# Controller_Board_Interface.net
KiCad netlist of a schematic drawn in Altium Designer
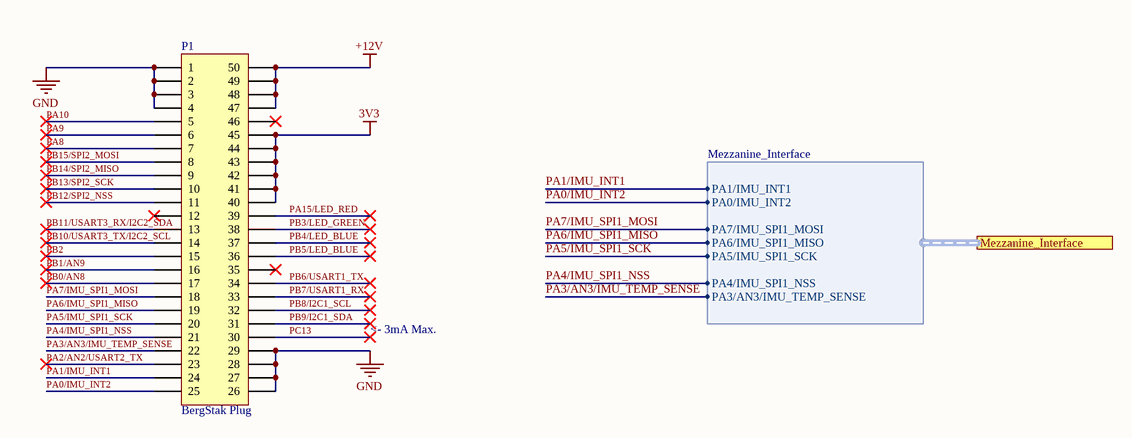
[diagram p0: Controller_Board_Interface.SchDoc]

(export (version "E")
  (design (tool "Eeschema 10.0.6"))
  (components
    (comp (ref "P1")
      (value "CONN 50POS Bergstak Plug 0.02\"")
      (footprint "CONN, Bergstak 50 Pos Plug")
      (description "50 Position Connector Plug, Outer Shroud Contacts Surface Mount Gold")
      (fields (field (name "SERIES") "BergStak Plug"))
      (libsource (lib "Schematic Diagrams") (part "CONN 50POS Bergstak Plug 0.02{dblquote}"))
    )
  )
  (nets
    (net (code "2") (name "+12V") (class "Default")
      (node (ref "P1") (pin "47") (pinfunction "47_47") (pintype "passive"))
      (node (ref "P1") (pin "48") (pinfunction "48_48") (pintype "passive"))
      (node (ref "P1") (pin "49") (pinfunction "49_49") (pintype "passive"))
      (node (ref "P1") (pin "50") (pinfunction "50_50") (pintype "passive"))
    )
    (net (code "3") (name "/PA0{slash}IMU_INT2") (class "Default")
      (node (ref "P1") (pin "25") (pinfunction "25_25") (pintype "passive"))
    )
    (net (code "4") (name "/PA1{slash}IMU_INT1") (class "Default")
      (node (ref "P1") (pin "24") (pinfunction "24_24") (pintype "passive"))
    )
    (net (code "5") (name "/PA2{slash}AN2{slash}USART2_TX") (class "Default")
      (node (ref "P1") (pin "23") (pinfunction "23_23") (pintype "passive+no_connect"))
    )
    (net (code "6") (name "/PA3{slash}AN3{slash}IMU_TEMP_SENSE") (class "Default")
      (node (ref "P1") (pin "22") (pinfunction "22_22") (pintype "passive"))
    )
    (net (code "7") (name "/PA4{slash}IMU_SPI1_NSS") (class "Default")
      (node (ref "P1") (pin "21") (pinfunction "21_21") (pintype "passive"))
    )
    (net (code "8") (name "/PA5{slash}IMU_SPI1_SCK") (class "Default")
      (node (ref "P1") (pin "20") (pinfunction "20_20") (pintype "passive"))
    )
    (net (code "9") (name "/PA6{slash}IMU_SPI1_MISO") (class "Default")
      (node (ref "P1") (pin "19") (pinfunction "19_19") (pintype "passive"))
    )
    (net (code "10") (name "/PA7{slash}IMU_SPI1_MOSI") (class "Default")
      (node (ref "P1") (pin "18") (pinfunction "18_18") (pintype "passive"))
    )
    (net (code "11") (name "/PA8") (class "Default")
      (node (ref "P1") (pin "7") (pinfunction "7_7") (pintype "passive+no_connect"))
    )
    (net (code "12") (name "/PA9") (class "Default")
      (node (ref "P1") (pin "6") (pinfunction "6_6") (pintype "passive+no_connect"))
    )
    (net (code "13") (name "/PA10") (class "Default")
      (node (ref "P1") (pin "5") (pinfunction "5_5") (pintype "passive+no_connect"))
    )
    (net (code "14") (name "/PA15{slash}LED_RED") (class "Default")
      (node (ref "P1") (pin "39") (pinfunction "39_39") (pintype "passive+no_connect"))
    )
    (net (code "15") (name "/PB0{slash}AN8") (class "Default")
      (node (ref "P1") (pin "17") (pinfunction "17_17") (pintype "passive+no_connect"))
    )
    (net (code "16") (name "/PB1{slash}AN9") (class "Default")
      (node (ref "P1") (pin "16") (pinfunction "16_16") (pintype "passive+no_connect"))
    )
    (net (code "17") (name "/PB2") (class "Default")
      (node (ref "P1") (pin "15") (pinfunction "15_15") (pintype "passive+no_connect"))
    )
    (net (code "18") (name "/PB3{slash}LED_GREEN") (class "Default")
      (node (ref "P1") (pin "38") (pinfunction "38_38") (pintype "passive+no_connect"))
    )
    (net (code "19") (name "/PB4{slash}LED_BLUE") (class "Default")
      (node (ref "P1") (pin "37") (pinfunction "37_37") (pintype "passive+no_connect"))
    )
    (net (code "20") (name "/PB5{slash}LED_BLUE") (class "Default")
      (node (ref "P1") (pin "36") (pinfunction "36_36") (pintype "passive+no_connect"))
    )
    (net (code "21") (name "/PB6{slash}USART1_TX") (class "Default")
      (node (ref "P1") (pin "34") (pinfunction "34_34") (pintype "passive+no_connect"))
    )
    (net (code "22") (name "/PB7{slash}USART1_RX") (class "Default")
      (node (ref "P1") (pin "33") (pinfunction "33_33") (pintype "passive+no_connect"))
    )
    (net (code "23") (name "/PB8{slash}I2C1_SCL") (class "Default")
      (node (ref "P1") (pin "32") (pinfunction "32_32") (pintype "passive+no_connect"))
    )
    (net (code "24") (name "/PB9{slash}I2C1_SDA") (class "Default")
      (node (ref "P1") (pin "31") (pinfunction "31_31") (pintype "passive+no_connect"))
    )
    (net (code "25") (name "/PB10{slash}USART3_TX{slash}I2C2_SCL") (class "Default")
      (node (ref "P1") (pin "14") (pinfunction "14_14") (pintype "passive+no_connect"))
    )
    (net (code "26") (name "/PB11{slash}USART3_RX{slash}I2C2_SDA") (class "Default")
      (node (ref "P1") (pin "13") (pinfunction "13_13") (pintype "passive+no_connect"))
    )
    (net (code "27") (name "/PB12{slash}SPI2_NSS") (class "Default")
      (node (ref "P1") (pin "11") (pinfunction "11_11") (pintype "passive+no_connect"))
    )
    (net (code "28") (name "/PB13{slash}SPI2_SCK") (class "Default")
      (node (ref "P1") (pin "10") (pinfunction "10_10") (pintype "passive+no_connect"))
    )
    (net (code "29") (name "/PB14{slash}SPI2_MISO") (class "Default")
      (node (ref "P1") (pin "9") (pinfunction "9_9") (pintype "passive+no_connect"))
    )
    (net (code "30") (name "/PB15{slash}SPI2_MOSI") (class "Default")
      (node (ref "P1") (pin "8") (pinfunction "8_8") (pintype "passive+no_connect"))
    )
    (net (code "31") (name "/PC13") (class "Default")
      (node (ref "P1") (pin "30") (pinfunction "30_30") (pintype "passive+no_connect"))
    )
    (net (code "33") (name "3V3") (class "Default")
      (node (ref "P1") (pin "40") (pinfunction "40_40") (pintype "passive"))
      (node (ref "P1") (pin "41") (pinfunction "41_41") (pintype "passive"))
      (node (ref "P1") (pin "42") (pinfunction "42_42") (pintype "passive"))
      (node (ref "P1") (pin "43") (pinfunction "43_43") (pintype "passive"))
      (node (ref "P1") (pin "44") (pinfunction "44_44") (pintype "passive"))
      (node (ref "P1") (pin "45") (pinfunction "45_45") (pintype "passive"))
    )
    (net (code "34") (name "GND") (class "Default")
      (node (ref "P1") (pin "1") (pinfunction "1_1") (pintype "passive"))
      (node (ref "P1") (pin "2") (pinfunction "2_2") (pintype "passive"))
      (node (ref "P1") (pin "26") (pinfunction "26_26") (pintype "passive"))
      (node (ref "P1") (pin "27") (pinfunction "27_27") (pintype "passive"))
      (node (ref "P1") (pin "28") (pinfunction "28_28") (pintype "passive"))
      (node (ref "P1") (pin "29") (pinfunction "29_29") (pintype "passive"))
      (node (ref "P1") (pin "3") (pinfunction "3_3") (pintype "passive"))
      (node (ref "P1") (pin "4") (pinfunction "4_4") (pintype "passive"))
    )
    (net (code "35") (name "unconnected-(P1-Pad12)") (class "Default")
      (node (ref "P1") (pin "12") (pinfunction "12_12") (pintype "passive+no_connect"))
    )
    (net (code "36") (name "unconnected-(P1-Pad35)") (class "Default")
      (node (ref "P1") (pin "35") (pinfunction "35_35") (pintype "passive+no_connect"))
    )
    (net (code "37") (name "unconnected-(P1-Pad46)") (class "Default")
      (node (ref "P1") (pin "46") (pinfunction "46_46") (pintype "passive+no_connect"))
    )
  )
)
